# Poactuator_Connectors.net
KiCad netlist of a schematic drawn in Altium Designer
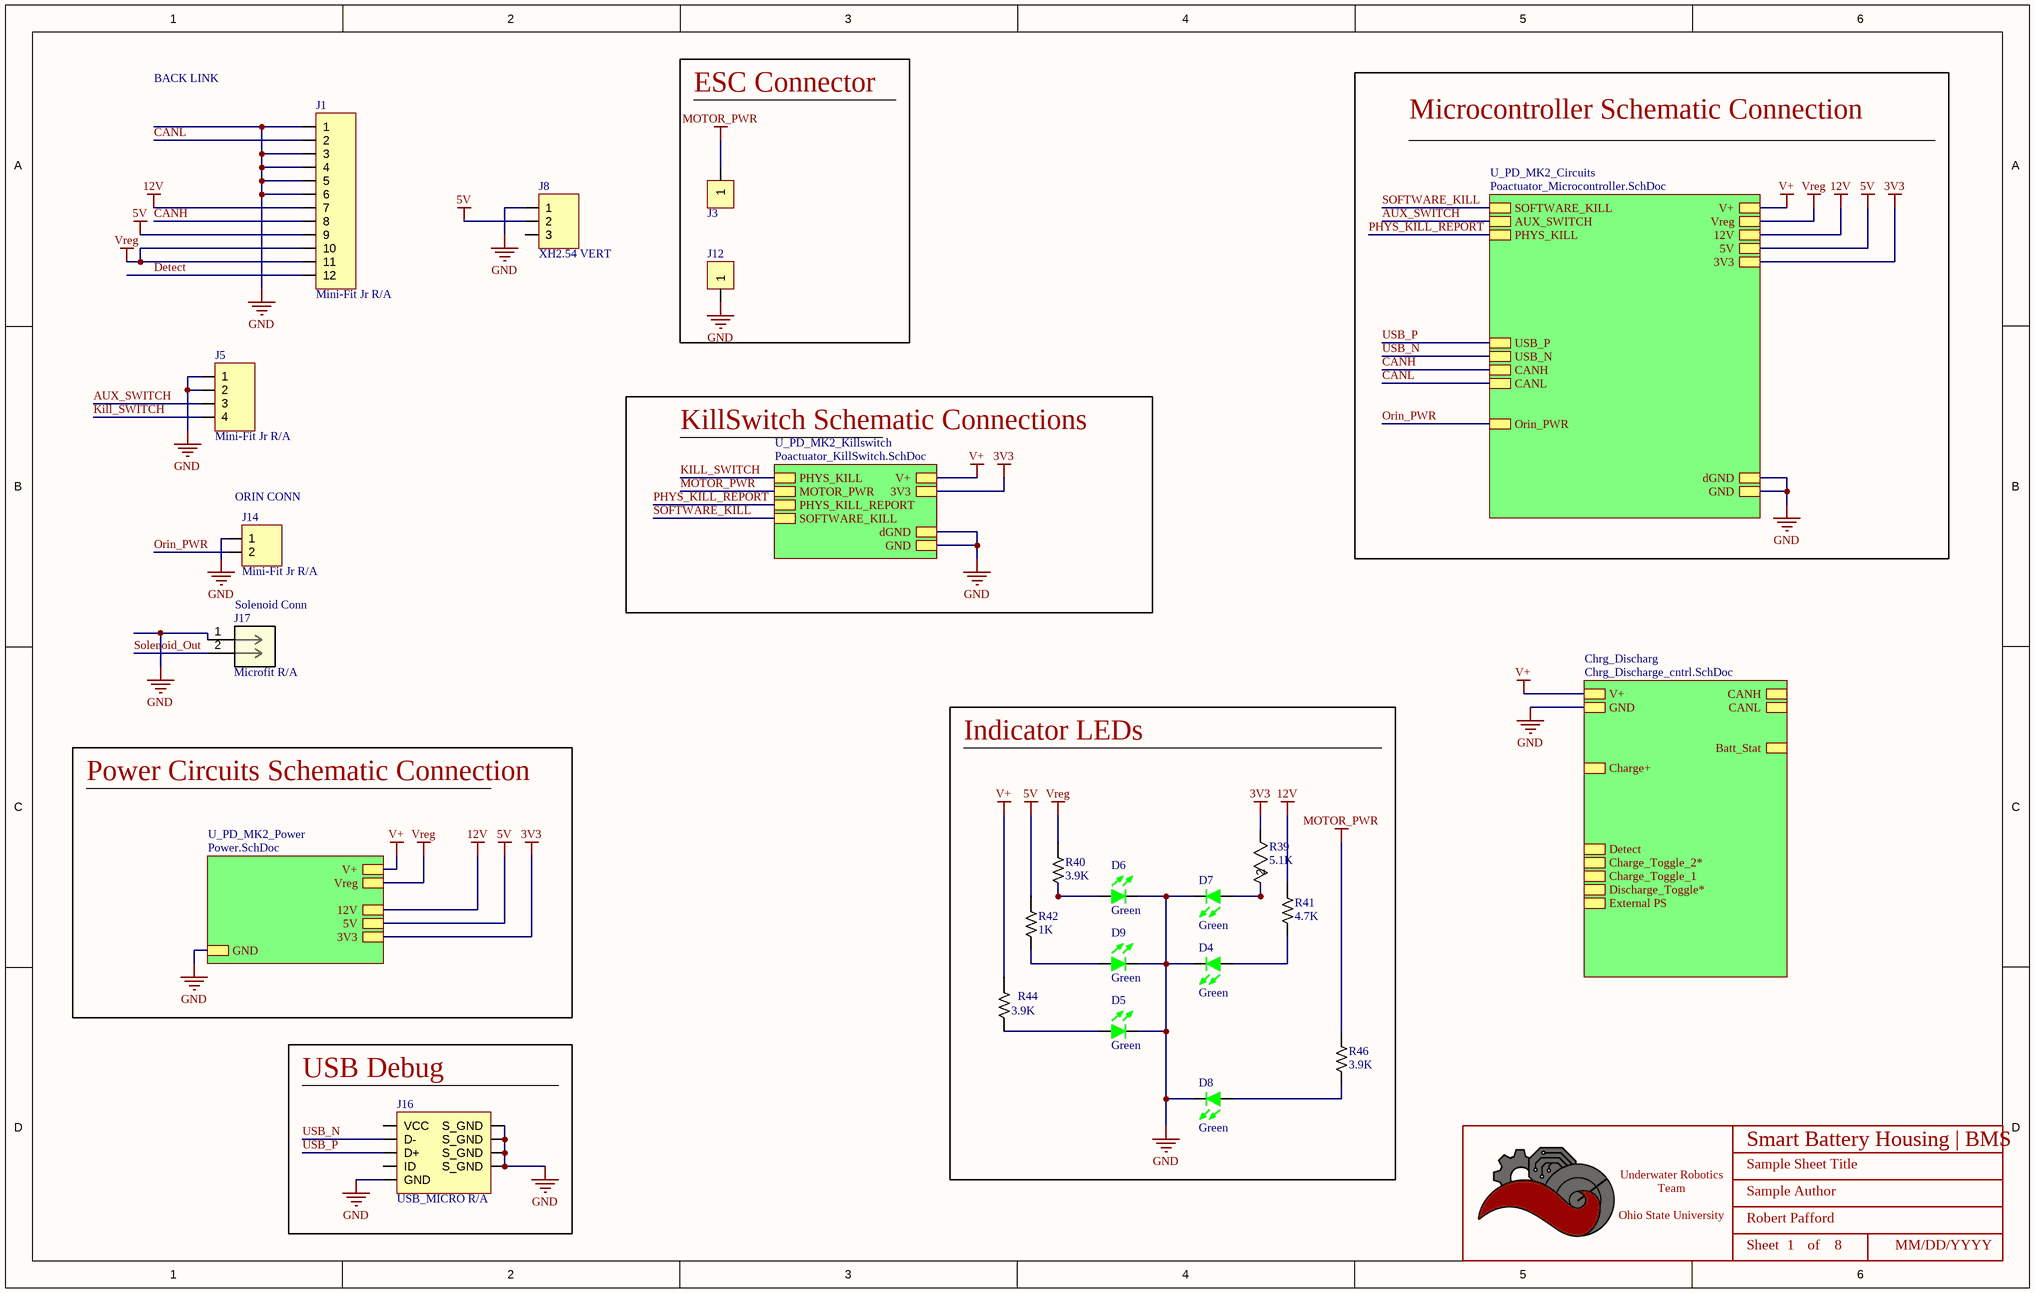
[diagram p0: Poactuator_Connectors.SchDoc]

(export (version "E")
  (design (tool "Eeschema 10.0.6"))
  (components
    (comp (ref "D4")
      (value "IN-S63AT5G")
      (footprint "LED_0603")
      (description "LED Green Vf= 3V If = 0.005A\r\nIN-S63AT5G")
      (fields (field (name "COLOR") "Green") (field (name "MADE BY") "Robert Pafford"))
      (libsource (lib "Diodes") (part "LED_Green_0603_3V"))
    )
    (comp (ref "D5")
      (value "IN-S63AT5G")
      (footprint "LED_0603")
      (description "LED Green Vf= 3V If = 0.005A\r\nIN-S63AT5G")
      (fields (field (name "COLOR") "Green") (field (name "MADE BY") "Robert Pafford"))
      (libsource (lib "Diodes") (part "LED_Green_0603_3V"))
    )
    (comp (ref "D6")
      (value "IN-S63AT5G")
      (footprint "LED_0603")
      (description "LED Green Vf= 3V If = 0.005A\r\nIN-S63AT5G")
      (fields (field (name "COLOR") "Green") (field (name "MADE BY") "Robert Pafford"))
      (libsource (lib "Diodes") (part "LED_Green_0603_3V"))
    )
    (comp (ref "D7")
      (value "IN-S63AT5G")
      (footprint "LED_0603")
      (description "LED Green Vf= 3V If = 0.005A\r\nIN-S63AT5G")
      (fields (field (name "COLOR") "Green") (field (name "MADE BY") "Robert Pafford"))
      (libsource (lib "Diodes") (part "LED_Green_0603_3V"))
    )
    (comp (ref "D8")
      (value "IN-S63AT5G")
      (footprint "LED_0603")
      (description "LED Green Vf= 3V If = 0.005A\r\nIN-S63AT5G")
      (fields (field (name "COLOR") "Green") (field (name "MADE BY") "Robert Pafford"))
      (libsource (lib "Diodes") (part "LED_Green_0603_3V"))
    )
    (comp (ref "D9")
      (value "IN-S63AT5G")
      (footprint "LED_0603")
      (description "LED Green Vf= 3V If = 0.005A\r\nIN-S63AT5G")
      (fields (field (name "COLOR") "Green") (field (name "MADE BY") "Robert Pafford"))
      (libsource (lib "Diodes") (part "LED_Green_0603_3V"))
    )
    (comp (ref "J1")
      (value "Mini-Fit Jr R/A")
      (footprint "CONN_MOLEX_MINIFIT JR_12 POS_R/A")
      (description "Molex Minifit Jr. 5569 \r\n12 Pos R/A Natural")
      (fields (field (name "MANUFACTURER") "Molex") (field (name "CREATED BY") "Flip B"))
      (libsource (lib "Connectors") (part "CONN_MOLEX_MINIFIT JR_12POS_R/A"))
    )
    (comp (ref "J3")
      (value "Redcube M4 Term 85A")
      (footprint "Redcube M4 Term 85A")
      (fields (field (name "CREATED BY") "Nahtan Ayer"))
      (libsource (lib "Connectors") (part "Redcube M4 Term 85A"))
    )
    (comp (ref "J5")
      (value "Mini-Fit Jr R/A")
      (footprint "CONN_MOLEX_MINIFIT JR_4 POS_R/A")
      (description "Molex Minifit Jr. 5569 \r\n4 Pos R/A Natural")
      (fields (field (name "MANUFACTURER") "Molex") (field (name "CREATED BY") "Flip B"))
      (libsource (lib "Connectors") (part "CONN_MOLEX_MINIFIT JR_4POS_R/A"))
    )
    (comp (ref "J8")
      (value "XH2.54 VERT")
      (footprint "CONN_JST_XH254_3POS_VERT")
      (description "JST XH 2.54mm Pitch 3 Pos Vertical")
      (fields (field (name "MANUFACTURER") "JST") (field (name "CREATED BY") "Robert P"))
      (libsource (lib "Connectors") (part "CONN_JST_XH254_3POS_VERT"))
    )
    (comp (ref "J12")
      (value "Redcube M4 Term 85A")
      (footprint "Redcube M4 Term 85A")
      (fields (field (name "CREATED BY") "Nahtan Ayer"))
      (libsource (lib "") (part "Redcube M4 Term 85A_1"))
    )
    (comp (ref "J14")
      (value "Mini-Fit Jr R/A")
      (footprint "CONN_MOLEX_MINIFIT JR_2 POS_R/A")
      (description "Molex Minifit Jr. 5569 \r\n2 Pos R/A Natural")
      (fields (field (name "MANUFACTURER") "Molex") (field (name "CREATED BY") "Robert P"))
      (libsource (lib "Connectors") (part "CONN_MOLEX_MINIFIT JR_2POS_R/A"))
    )
    (comp (ref "J16")
      (value "USB_MICRO R/A")
      (footprint "CONN_MINIUSB")
      (description "Amphenol Micro USB-B\r\nUSB2.0 5 Pin Right Angle SMD")
      (fields (field (name "MANUFACTURER") "Amphenol") (field (name "CREATED BY") "Flip B"))
      (libsource (lib "Connectors") (part "CONN_MICROUSB"))
    )
    (comp (ref "J17")
      (value "Microfit R/A")
      (footprint "CONN_MOLEX_MICROFIT_2 POS_R/A")
      (description "CONN HEADER R/A 2POS")
      (fields (field (name "MANUFACTURER") "Molex"))
      (libsource (lib "Connectors") (part "CONN_MOLEX_MICROFIT_2 POS_R/A"))
    )
    (comp (ref "R39")
      (value "5.1K")
      (footprint "RESISTOR_0603")
      (description "5.1 kOhms ±0.1% 0.1W, 1/10W Chip Resistor 0603 (1608 Metric) Automotive AEC-Q200 Thin Film")
      (fields
        (field (name "MANUFACTURER_PART_NUMBER") "ERA-3AEB512V")
        (field (name "COPYRIGHT") "Copyright (C) 2023 Ultra Librarian. All rights reserved.")
      )
      (libsource (lib "Resistors") (part "ERA-3AEB512V_2"))
    )
    (comp (ref "R40")
      (value "3.9k Ohm 5% 1/10W")
      (footprint "RESISTOR_0603")
      (description "RES 3.9k OHM 1% 1/10W 0603")
      (fields
        (field (name "TOLERANCE") "+/- 1%")
        (field (name "VALUE  (OHMS)") "3.9K")
        (field (name "MADE BY") "Robert Pafford")
      )
      (libsource (lib "Resistors") (part "RESISTOR_3.9K_0603"))
    )
    (comp (ref "R41")
      (value "4.7k Ohm 5% 1/10W")
      (footprint "RESISTOR_0603")
      (description "RES 4.7k OHM 5% 1/10W 0603")
      (fields
        (field (name "TOLERANCE") "+/- 5%")
        (field (name "VALUE  (OHMS)") "4.7K")
        (field (name "MADE BY") "Robert Pafford")
      )
      (libsource (lib "Resistors") (part "RESISTOR_4.7K_0603"))
    )
    (comp (ref "R42")
      (value "1k Ohm 5% 1/8W")
      (footprint "RESISTOR_0603")
      (description "RES 1k OHM 5% 1/8W 0603")
      (fields
        (field (name "TOLERANCE") "+/- 5%")
        (field (name "VALUE  (OHMS)") "1K")
        (field (name "MADE BY") "Robert Pafford")
      )
      (libsource (lib "Resistors") (part "RESISTOR_1K_0603"))
    )
    (comp (ref "R44")
      (value "3.9k Ohm 5% 1/10W")
      (footprint "RESISTOR_0603")
      (description "RES 3.9k OHM 1% 1/10W 0603")
      (fields
        (field (name "TOLERANCE") "+/- 1%")
        (field (name "VALUE  (OHMS)") "3.9K")
        (field (name "MADE BY") "Robert Pafford")
      )
      (libsource (lib "Resistors") (part "RESISTOR_3.9K_0603"))
    )
    (comp (ref "R46")
      (value "3.9k Ohm 5% 1/10W")
      (footprint "RESISTOR_0603")
      (description "RES 3.9k OHM 1% 1/10W 0603")
      (fields
        (field (name "TOLERANCE") "+/- 1%")
        (field (name "VALUE  (OHMS)") "3.9K")
        (field (name "MADE BY") "Robert Pafford")
      )
      (libsource (lib "Resistors") (part "RESISTOR_3.9K_0603"))
    )
  )
  (nets
    (net (code "1") (name "/AUX_SWITCH") (class "Default")
      (node (ref "J5") (pin "3") (pinfunction "3_3") (pintype "passive"))
    )
    (net (code "3") (name "/CANH") (class "Default")
      (node (ref "J1") (pin "8") (pinfunction "8_8") (pintype "passive"))
    )
    (net (code "5") (name "/CANL") (class "Default")
      (node (ref "J1") (pin "2") (pinfunction "2_2") (pintype "passive"))
    )
    (net (code "10") (name "/Detect") (class "Default")
      (node (ref "J1") (pin "12") (pinfunction "12_12") (pintype "passive"))
    )
    (net (code "15") (name "/Kill_SWITCH") (class "Default")
      (node (ref "J5") (pin "4") (pinfunction "4_4") (pintype "passive"))
    )
    (net (code "16") (name "/Orin_PWR") (class "Default")
      (node (ref "J14") (pin "2") (pinfunction "2_2") (pintype "passive"))
    )
    (net (code "19") (name "/Solenoid_Out") (class "Default")
      (node (ref "J17") (pin "2") (pinfunction "2_2") (pintype "passive"))
    )
    (net (code "20") (name "/USB_N") (class "Default")
      (node (ref "J16") (pin "2") (pinfunction "D-_2") (pintype "passive"))
    )
    (net (code "21") (name "/USB_P") (class "Default")
      (node (ref "J16") (pin "3") (pinfunction "D+_3") (pintype "passive"))
    )
    (net (code "22") (name "3V3") (class "Default")
      (node (ref "R39") (pin "1") (pinfunction "1_1") (pintype "passive"))
    )
    (net (code "23") (name "5V") (class "Default")
      (node (ref "J1") (pin "9") (pinfunction "9_9") (pintype "passive"))
      (node (ref "J8") (pin "2") (pinfunction "2_2") (pintype "passive"))
      (node (ref "R42") (pin "1") (pinfunction "1_1") (pintype "passive"))
    )
    (net (code "24") (name "12V") (class "Default")
      (node (ref "J1") (pin "7") (pinfunction "7_7") (pintype "passive"))
      (node (ref "R41") (pin "1") (pinfunction "1_1") (pintype "passive"))
    )
    (net (code "25") (name "GND") (class "Default")
      (node (ref "D4") (pin "2") (pinfunction "2_2") (pintype "passive"))
      (node (ref "D5") (pin "2") (pinfunction "2_2") (pintype "passive"))
      (node (ref "D6") (pin "2") (pinfunction "2_2") (pintype "passive"))
      (node (ref "D7") (pin "2") (pinfunction "2_2") (pintype "passive"))
      (node (ref "D8") (pin "2") (pinfunction "2_2") (pintype "passive"))
      (node (ref "D9") (pin "2") (pinfunction "2_2") (pintype "passive"))
      (node (ref "J1") (pin "1") (pinfunction "1_1") (pintype "passive"))
      (node (ref "J1") (pin "3") (pinfunction "3_3") (pintype "passive"))
      (node (ref "J1") (pin "4") (pinfunction "4_4") (pintype "passive"))
      (node (ref "J1") (pin "5") (pinfunction "5_5") (pintype "passive"))
      (node (ref "J1") (pin "6") (pinfunction "6_6") (pintype "passive"))
      (node (ref "J12") (pin "1") (pinfunction "1_1") (pintype "passive"))
      (node (ref "J14") (pin "1") (pinfunction "1_1") (pintype "passive"))
      (node (ref "J16") (pin "5") (pinfunction "GND_5") (pintype "passive"))
      (node (ref "J16") (pin "6") (pinfunction "S_GND_6") (pintype "passive"))
      (node (ref "J16") (pin "7") (pinfunction "S_GND_7") (pintype "passive"))
      (node (ref "J16") (pin "8") (pinfunction "S_GND_8") (pintype "passive"))
      (node (ref "J16") (pin "9") (pinfunction "S_GND_9") (pintype "passive"))
      (node (ref "J17") (pin "1") (pinfunction "1_1") (pintype "passive"))
      (node (ref "J5") (pin "1") (pinfunction "1_1") (pintype "passive"))
      (node (ref "J5") (pin "2") (pinfunction "2_2") (pintype "passive"))
      (node (ref "J8") (pin "1") (pinfunction "1_1") (pintype "passive"))
    )
    (net (code "26") (name "MOTOR_PWR") (class "Default")
      (node (ref "J3") (pin "1") (pinfunction "1_1") (pintype "passive"))
      (node (ref "R46") (pin "1") (pinfunction "1_1") (pintype "passive"))
    )
    (net (code "27") (name "Net-(D4-Pad1)") (class "Default")
      (node (ref "D4") (pin "1") (pinfunction "1_1") (pintype "passive"))
      (node (ref "R41") (pin "2") (pinfunction "2_2") (pintype "passive"))
    )
    (net (code "28") (name "Net-(D5-Pad1)") (class "Default")
      (node (ref "D5") (pin "1") (pinfunction "1_1") (pintype "passive"))
      (node (ref "R44") (pin "2") (pinfunction "2_2") (pintype "passive"))
    )
    (net (code "29") (name "Net-(D6-Pad1)") (class "Default")
      (node (ref "D6") (pin "1") (pinfunction "1_1") (pintype "passive"))
      (node (ref "R40") (pin "2") (pinfunction "2_2") (pintype "passive"))
    )
    (net (code "30") (name "Net-(D7-Pad1)") (class "Default")
      (node (ref "D7") (pin "1") (pinfunction "1_1") (pintype "passive"))
      (node (ref "R39") (pin "2") (pinfunction "2_2") (pintype "passive"))
    )
    (net (code "31") (name "Net-(D8-Pad1)") (class "Default")
      (node (ref "D8") (pin "1") (pinfunction "1_1") (pintype "passive"))
      (node (ref "R46") (pin "2") (pinfunction "2_2") (pintype "passive"))
    )
    (net (code "32") (name "Net-(D9-Pad1)") (class "Default")
      (node (ref "D9") (pin "1") (pinfunction "1_1") (pintype "passive"))
      (node (ref "R42") (pin "2") (pinfunction "2_2") (pintype "passive"))
    )
    (net (code "33") (name "V+") (class "Default")
      (node (ref "R44") (pin "1") (pinfunction "1_1") (pintype "passive"))
    )
    (net (code "34") (name "Vreg") (class "Default")
      (node (ref "J1") (pin "10") (pinfunction "10_10") (pintype "passive"))
      (node (ref "J1") (pin "11") (pinfunction "11_11") (pintype "passive"))
      (node (ref "R40") (pin "1") (pinfunction "1_1") (pintype "passive"))
    )
    (net (code "35") (name "unconnected-(J8-Pad3)") (class "Default")
      (node (ref "J8") (pin "3") (pinfunction "3_3") (pintype "passive"))
    )
    (net (code "36") (name "unconnected-(J16-ID-Pad4)") (class "Default")
      (node (ref "J16") (pin "4") (pinfunction "ID_4") (pintype "passive"))
    )
    (net (code "37") (name "unconnected-(J16-VCC-Pad1)") (class "Default")
      (node (ref "J16") (pin "1") (pinfunction "VCC_1") (pintype "passive"))
    )
  )
)
